# Frankie_DIYRevC.net
KiCad netlist of a schematic drawn in EAGLE
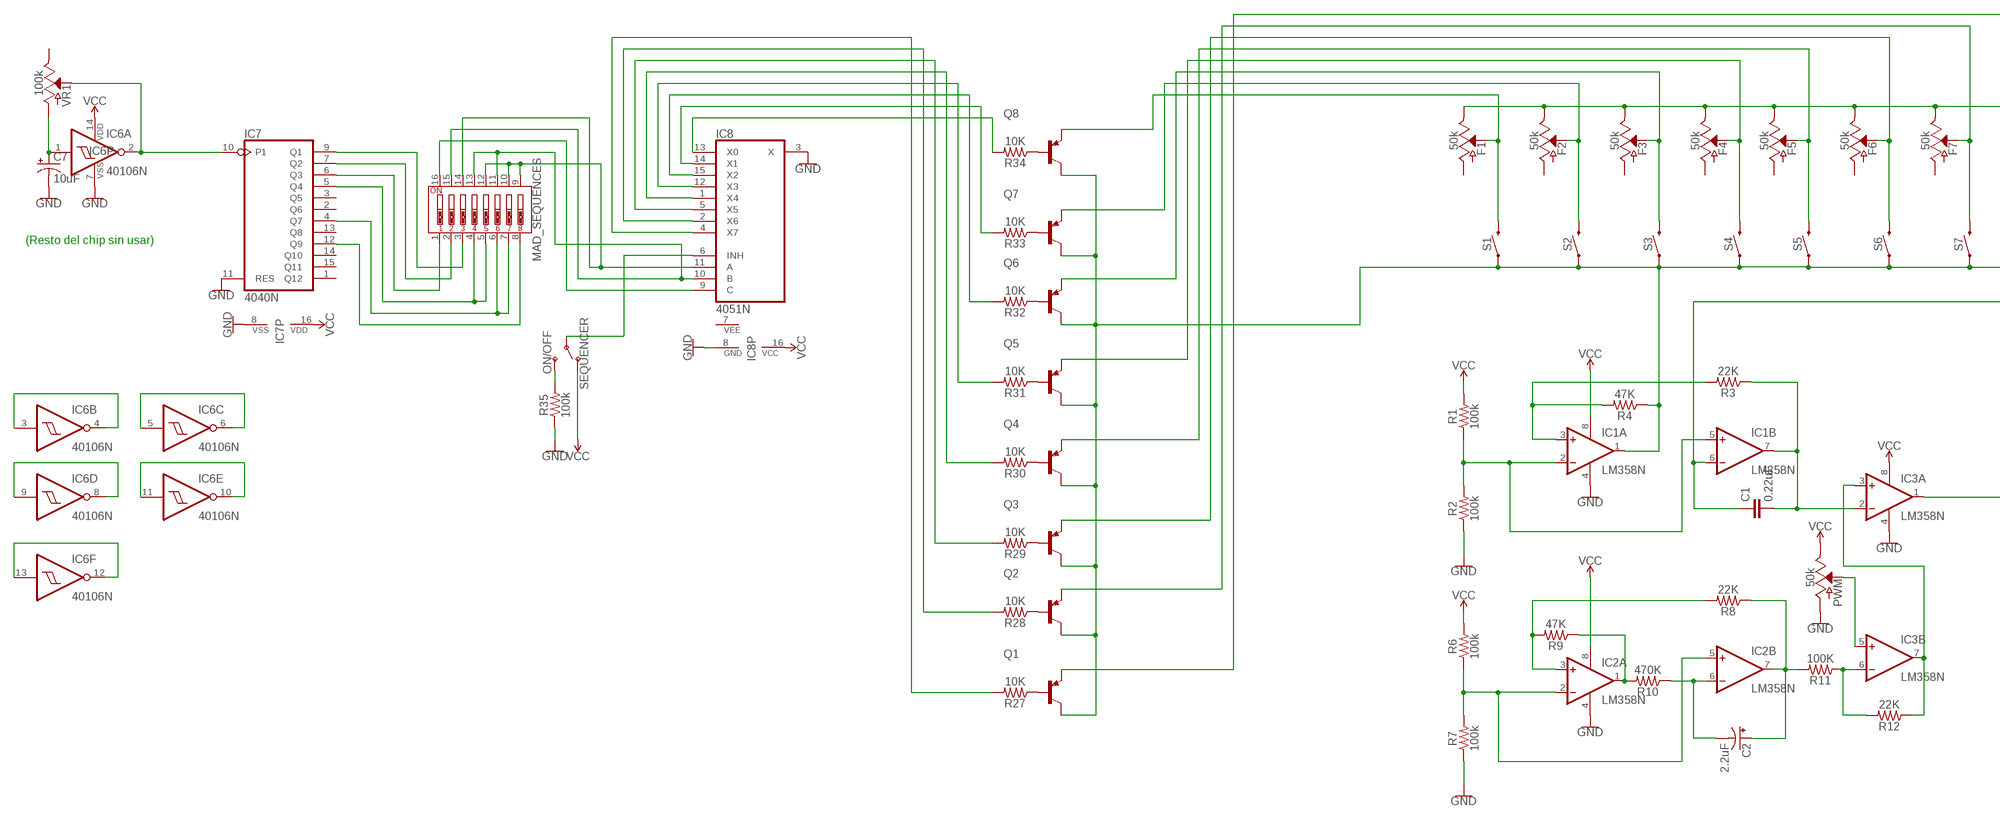
[diagram p0: schematic, sheet 1, part 1 of 2]
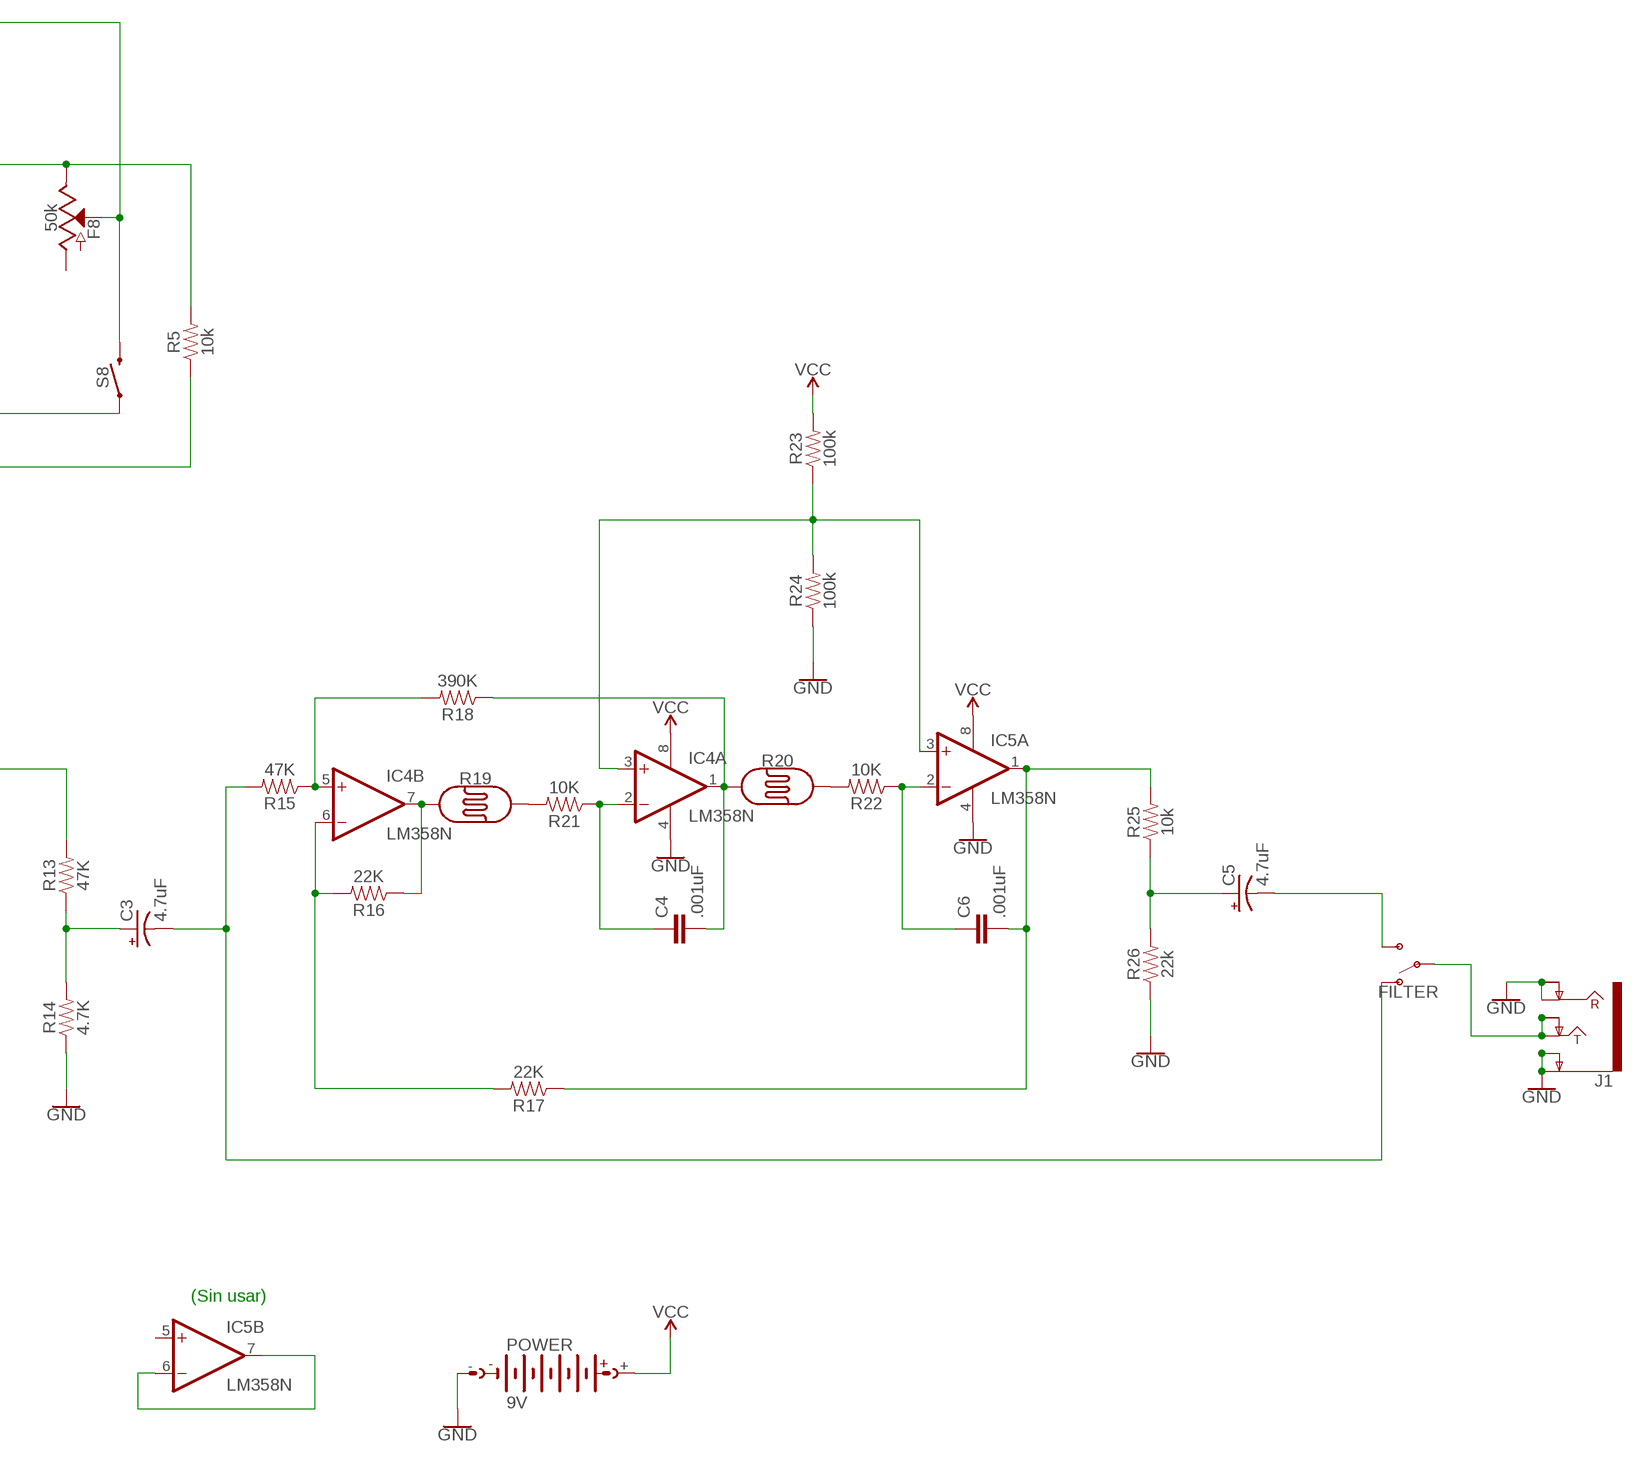
[diagram p1: schematic, sheet 1, part 2 of 2]

(export (version "E")
  (design (tool "Eeschema 10.0.6"))
  (components
    (comp (ref "C1")
      (value "0.22uF")
      (footprint "eagle-import:C5B2.5")
      (libsource (lib "eagle-import") (part "C5/2.5"))
    )
    (comp (ref "C2")
      (value "2.2uF")
      (footprint "eagle-import:CPOL-RADIAL-2.5MM-5MM-KIT")
      (libsource (lib "eagle-import") (part "10UF-POLAR-RADIAL-2.5MM-KIT-25V-20%"))
    )
    (comp (ref "C3")
      (value "4.7uF")
      (footprint "eagle-import:CPOL-RADIAL-2.5MM-5MM-KIT")
      (libsource (lib "eagle-import") (part "10UF-POLAR-RADIAL-2.5MM-KIT-25V-20%"))
    )
    (comp (ref "C4")
      (value ".001uF")
      (footprint "eagle-import:C5B2.5")
      (libsource (lib "eagle-import") (part "C5/2.5"))
    )
    (comp (ref "C5")
      (value "4.7uF")
      (footprint "eagle-import:CPOL-RADIAL-2.5MM-5MM-KIT")
      (libsource (lib "eagle-import") (part "10UF-POLAR-RADIAL-2.5MM-KIT-25V-20%"))
    )
    (comp (ref "C6")
      (value ".001uF")
      (footprint "eagle-import:C5B2.5")
      (libsource (lib "eagle-import") (part "C5/2.5"))
    )
    (comp (ref "C7")
      (value "10uF")
      (footprint "eagle-import:CPOL-RADIAL-2.5MM-5MM-KIT")
      (libsource (lib "eagle-import") (part "10UF-POLAR-RADIAL-2.5MM-KIT-25V-20%"))
    )
    (comp (ref "F1")
      (value "50k")
      (footprint "eagle-import:POT-PTH-ALPS-KIT")
      (libsource (lib "eagle-import") (part "POTENTIOMETER-PTH-9MM-1/20W-20%-KIT"))
    )
    (comp (ref "F2")
      (value "50k")
      (footprint "eagle-import:POT-PTH-ALPS-KIT")
      (libsource (lib "eagle-import") (part "POTENTIOMETER-PTH-9MM-1/20W-20%-KIT"))
    )
    (comp (ref "F3")
      (value "50k")
      (footprint "eagle-import:POT-PTH-ALPS-KIT")
      (libsource (lib "eagle-import") (part "POTENTIOMETER-PTH-9MM-1/20W-20%-KIT"))
    )
    (comp (ref "F4")
      (value "50k")
      (footprint "eagle-import:POT-PTH-ALPS-KIT")
      (libsource (lib "eagle-import") (part "POTENTIOMETER-PTH-9MM-1/20W-20%-KIT"))
    )
    (comp (ref "F5")
      (value "50k")
      (footprint "eagle-import:POT-PTH-ALPS-KIT")
      (libsource (lib "eagle-import") (part "POTENTIOMETER-PTH-9MM-1/20W-20%-KIT"))
    )
    (comp (ref "F6")
      (value "50k")
      (footprint "eagle-import:POT-PTH-ALPS-KIT")
      (libsource (lib "eagle-import") (part "POTENTIOMETER-PTH-9MM-1/20W-20%-KIT"))
    )
    (comp (ref "F7")
      (value "50k")
      (footprint "eagle-import:POT-PTH-ALPS-KIT")
      (libsource (lib "eagle-import") (part "POTENTIOMETER-PTH-9MM-1/20W-20%-KIT"))
    )
    (comp (ref "F8")
      (value "50k")
      (footprint "eagle-import:POT-PTH-ALPS-KIT")
      (libsource (lib "eagle-import") (part "POTENTIOMETER-PTH-9MM-1/20W-20%-KIT"))
    )
    (comp (ref "FILTER")
      (value "SWITCH-SPDT-PTH-11.6X4.0MM-KIT")
      (footprint "eagle-import:SWITCH_SPDT_PTH_11.6X4.0MM_KIT")
      (libsource (lib "eagle-import") (part "SWITCH-SPDT-PTH-11.6X4.0MM-KIT"))
    )
    (comp (ref "IC1")
      (value "LM358N")
      (footprint "eagle-import:DIL08")
      (libsource (lib "eagle-import") (part "LM358N"))
    )
    (comp (ref "IC2")
      (value "LM358N")
      (footprint "eagle-import:DIL08")
      (libsource (lib "eagle-import") (part "LM358N"))
    )
    (comp (ref "IC3")
      (value "LM358N")
      (footprint "eagle-import:DIL08")
      (libsource (lib "eagle-import") (part "LM358N"))
    )
    (comp (ref "IC4")
      (value "LM358N")
      (footprint "eagle-import:DIL08")
      (libsource (lib "eagle-import") (part "LM358N"))
    )
    (comp (ref "IC5")
      (value "LM358N")
      (footprint "eagle-import:DIL08")
      (libsource (lib "eagle-import") (part "LM358N"))
    )
    (comp (ref "IC6")
      (value "40106N")
      (footprint "eagle-import:DIL14")
      (libsource (lib "eagle-import") (part "40106N"))
    )
    (comp (ref "IC7")
      (value "4040N")
      (footprint "eagle-import:DIL16")
      (libsource (lib "eagle-import") (part "4040N"))
    )
    (comp (ref "IC8")
      (value "4051N")
      (footprint "eagle-import:DIL16")
      (libsource (lib "eagle-import") (part "4051N"))
    )
    (comp (ref "J1")
      (value "AUDIO_JACK_TRS_0.25\"_PTH_RA")
      (footprint "eagle-import:AUDIO_JACK_0.25__TRS_PTH_RA")
      (libsource (lib "eagle-import") (part "AUDIO_JACK_TRS_0.25{dblquote}_PTH_RA"))
    )
    (comp (ref "MAD_SEQUENCES")
      (value "DIP-08-PTH")
      (footprint "eagle-import:DIPSWITCH-08")
      (libsource (lib "eagle-import") (part "DIP-08-PTH"))
    )
    (comp (ref "POWER")
      (value "9V")
      (footprint "eagle-import:AB9V")
      (libsource (lib "eagle-import") (part "AB9V"))
    )
    (comp (ref "PWM")
      (value "50k")
      (footprint "eagle-import:POT-PTH-ALPS-KIT")
      (libsource (lib "eagle-import") (part "POTENTIOMETER-PTH-9MM-1/20W-20%-KIT"))
    )
    (comp (ref "Q1")
      (value "2N3906")
      (footprint "eagle-import:TO92")
      (libsource (lib "eagle-import") (part "2N3906"))
    )
    (comp (ref "Q2")
      (value "2N3906")
      (footprint "eagle-import:TO92")
      (libsource (lib "eagle-import") (part "2N3906"))
    )
    (comp (ref "Q3")
      (value "2N3906")
      (footprint "eagle-import:TO92")
      (libsource (lib "eagle-import") (part "2N3906"))
    )
    (comp (ref "Q4")
      (value "2N3906")
      (footprint "eagle-import:TO92")
      (libsource (lib "eagle-import") (part "2N3906"))
    )
    (comp (ref "Q5")
      (value "2N3906")
      (footprint "eagle-import:TO92")
      (libsource (lib "eagle-import") (part "2N3906"))
    )
    (comp (ref "Q6")
      (value "2N3906")
      (footprint "eagle-import:TO92")
      (libsource (lib "eagle-import") (part "2N3906"))
    )
    (comp (ref "Q7")
      (value "2N3906")
      (footprint "eagle-import:TO92")
      (libsource (lib "eagle-import") (part "2N3906"))
    )
    (comp (ref "Q8")
      (value "2N3906")
      (footprint "eagle-import:TO92")
      (libsource (lib "eagle-import") (part "2N3906"))
    )
    (comp (ref "R1")
      (value "100k")
      (footprint "eagle-import:AXIAL-0.3")
      (libsource (lib "eagle-import") (part "100KOHM-HORIZ-1/4W-5%"))
    )
    (comp (ref "R2")
      (value "100k")
      (footprint "eagle-import:AXIAL-0.3")
      (libsource (lib "eagle-import") (part "100KOHM-HORIZ-1/4W-5%"))
    )
    (comp (ref "R3")
      (value "22K")
      (footprint "eagle-import:AXIAL-0.3")
      (libsource (lib "eagle-import") (part "100KOHM-HORIZ-1/4W-5%"))
    )
    (comp (ref "R4")
      (value "47K")
      (footprint "eagle-import:AXIAL-0.3")
      (libsource (lib "eagle-import") (part "100KOHM-HORIZ-1/4W-5%"))
    )
    (comp (ref "R5")
      (value "10k")
      (footprint "eagle-import:AXIAL-0.3")
      (libsource (lib "eagle-import") (part "100KOHM-HORIZ-1/4W-5%"))
    )
    (comp (ref "R6")
      (value "100k")
      (footprint "eagle-import:AXIAL-0.3")
      (libsource (lib "eagle-import") (part "100KOHM-HORIZ-1/4W-5%"))
    )
    (comp (ref "R7")
      (value "100k")
      (footprint "eagle-import:AXIAL-0.3")
      (libsource (lib "eagle-import") (part "100KOHM-HORIZ-1/4W-5%"))
    )
    (comp (ref "R8")
      (value "22K")
      (footprint "eagle-import:AXIAL-0.3")
      (libsource (lib "eagle-import") (part "100KOHM-HORIZ-1/4W-5%"))
    )
    (comp (ref "R9")
      (value "47K")
      (footprint "eagle-import:AXIAL-0.3")
      (libsource (lib "eagle-import") (part "100KOHM-HORIZ-1/4W-5%"))
    )
    (comp (ref "R10")
      (value "470K")
      (footprint "eagle-import:AXIAL-0.3")
      (libsource (lib "eagle-import") (part "100KOHM-HORIZ-1/4W-5%"))
    )
    (comp (ref "R11")
      (value "100K")
      (footprint "eagle-import:AXIAL-0.3")
      (libsource (lib "eagle-import") (part "100KOHM-HORIZ-1/4W-5%"))
    )
    (comp (ref "R12")
      (value "22K")
      (footprint "eagle-import:AXIAL-0.3")
      (libsource (lib "eagle-import") (part "100KOHM-HORIZ-1/4W-5%"))
    )
    (comp (ref "R13")
      (value "47K")
      (footprint "eagle-import:AXIAL-0.3")
      (libsource (lib "eagle-import") (part "100KOHM-HORIZ-1/4W-5%"))
    )
    (comp (ref "R14")
      (value "4.7K")
      (footprint "eagle-import:AXIAL-0.3")
      (libsource (lib "eagle-import") (part "100KOHM-HORIZ-1/4W-5%"))
    )
    (comp (ref "R15")
      (value "47K")
      (footprint "eagle-import:AXIAL-0.3")
      (libsource (lib "eagle-import") (part "100KOHM-HORIZ-1/4W-5%"))
    )
    (comp (ref "R16")
      (value "22K")
      (footprint "eagle-import:AXIAL-0.3")
      (libsource (lib "eagle-import") (part "100KOHM-HORIZ-1/4W-5%"))
    )
    (comp (ref "R17")
      (value "22K")
      (footprint "eagle-import:AXIAL-0.3")
      (libsource (lib "eagle-import") (part "100KOHM-HORIZ-1/4W-5%"))
    )
    (comp (ref "R18")
      (value "390K")
      (footprint "eagle-import:AXIAL-0.3")
      (libsource (lib "eagle-import") (part "100KOHM-HORIZ-1/4W-5%"))
    )
    (comp (ref "R19")
      (value "PHOTOCELLPTH-KIT")
      (footprint "eagle-import:PHOTOCELL-KIT")
      (libsource (lib "eagle-import") (part "PHOTOCELLPTH-KIT"))
    )
    (comp (ref "R20")
      (value "PHOTOCELLPTH-KIT")
      (footprint "eagle-import:PHOTOCELL-KIT")
      (libsource (lib "eagle-import") (part "PHOTOCELLPTH-KIT"))
    )
    (comp (ref "R21")
      (value "10K")
      (footprint "eagle-import:AXIAL-0.3")
      (libsource (lib "eagle-import") (part "100KOHM-HORIZ-1/4W-5%"))
    )
    (comp (ref "R22")
      (value "10K")
      (footprint "eagle-import:AXIAL-0.3")
      (libsource (lib "eagle-import") (part "100KOHM-HORIZ-1/4W-5%"))
    )
    (comp (ref "R23")
      (value "100k")
      (footprint "eagle-import:AXIAL-0.3")
      (libsource (lib "eagle-import") (part "100KOHM-HORIZ-1/4W-5%"))
    )
    (comp (ref "R24")
      (value "100k")
      (footprint "eagle-import:AXIAL-0.3")
      (libsource (lib "eagle-import") (part "100KOHM-HORIZ-1/4W-5%"))
    )
    (comp (ref "R25")
      (value "10k")
      (footprint "eagle-import:AXIAL-0.3")
      (libsource (lib "eagle-import") (part "100KOHM-HORIZ-1/4W-5%"))
    )
    (comp (ref "R26")
      (value "22k")
      (footprint "eagle-import:AXIAL-0.3")
      (libsource (lib "eagle-import") (part "100KOHM-HORIZ-1/4W-5%"))
    )
    (comp (ref "R27")
      (value "10K")
      (footprint "eagle-import:AXIAL-0.3")
      (libsource (lib "eagle-import") (part "100KOHM-HORIZ-1/4W-5%"))
    )
    (comp (ref "R28")
      (value "10K")
      (footprint "eagle-import:AXIAL-0.3")
      (libsource (lib "eagle-import") (part "100KOHM-HORIZ-1/4W-5%"))
    )
    (comp (ref "R29")
      (value "10K")
      (footprint "eagle-import:AXIAL-0.3")
      (libsource (lib "eagle-import") (part "100KOHM-HORIZ-1/4W-5%"))
    )
    (comp (ref "R30")
      (value "10K")
      (footprint "eagle-import:AXIAL-0.3")
      (libsource (lib "eagle-import") (part "100KOHM-HORIZ-1/4W-5%"))
    )
    (comp (ref "R31")
      (value "10K")
      (footprint "eagle-import:AXIAL-0.3")
      (libsource (lib "eagle-import") (part "100KOHM-HORIZ-1/4W-5%"))
    )
    (comp (ref "R32")
      (value "10K")
      (footprint "eagle-import:AXIAL-0.3")
      (libsource (lib "eagle-import") (part "100KOHM-HORIZ-1/4W-5%"))
    )
    (comp (ref "R33")
      (value "10K")
      (footprint "eagle-import:AXIAL-0.3")
      (libsource (lib "eagle-import") (part "100KOHM-HORIZ-1/4W-5%"))
    )
    (comp (ref "R34")
      (value "10K")
      (footprint "eagle-import:AXIAL-0.3")
      (libsource (lib "eagle-import") (part "100KOHM-HORIZ-1/4W-5%"))
    )
    (comp (ref "R35")
      (value "100k")
      (footprint "eagle-import:AXIAL-0.3")
      (libsource (lib "eagle-import") (part "100KOHM-HORIZ-1/4W-5%"))
    )
    (comp (ref "S1")
      (value "MOMENTARY-SWITCH-SPST-PTH-12MM")
      (footprint "eagle-import:TACTILE_SWITCH_PTH_12MM")
      (libsource (lib "eagle-import") (part "MOMENTARY-SWITCH-SPST-PTH-12MM"))
    )
    (comp (ref "S2")
      (value "MOMENTARY-SWITCH-SPST-PTH-12MM")
      (footprint "eagle-import:TACTILE_SWITCH_PTH_12MM")
      (libsource (lib "eagle-import") (part "MOMENTARY-SWITCH-SPST-PTH-12MM"))
    )
    (comp (ref "S3")
      (value "MOMENTARY-SWITCH-SPST-PTH-12MM")
      (footprint "eagle-import:TACTILE_SWITCH_PTH_12MM")
      (libsource (lib "eagle-import") (part "MOMENTARY-SWITCH-SPST-PTH-12MM"))
    )
    (comp (ref "S4")
      (value "MOMENTARY-SWITCH-SPST-PTH-12MM")
      (footprint "eagle-import:TACTILE_SWITCH_PTH_12MM")
      (libsource (lib "eagle-import") (part "MOMENTARY-SWITCH-SPST-PTH-12MM"))
    )
    (comp (ref "S5")
      (value "MOMENTARY-SWITCH-SPST-PTH-12MM")
      (footprint "eagle-import:TACTILE_SWITCH_PTH_12MM")
      (libsource (lib "eagle-import") (part "MOMENTARY-SWITCH-SPST-PTH-12MM"))
    )
    (comp (ref "S6")
      (value "MOMENTARY-SWITCH-SPST-PTH-12MM")
      (footprint "eagle-import:TACTILE_SWITCH_PTH_12MM")
      (libsource (lib "eagle-import") (part "MOMENTARY-SWITCH-SPST-PTH-12MM"))
    )
    (comp (ref "S7")
      (value "MOMENTARY-SWITCH-SPST-PTH-12MM")
      (footprint "eagle-import:TACTILE_SWITCH_PTH_12MM")
      (libsource (lib "eagle-import") (part "MOMENTARY-SWITCH-SPST-PTH-12MM"))
    )
    (comp (ref "S8")
      (value "MOMENTARY-SWITCH-SPST-PTH-12MM")
      (footprint "eagle-import:TACTILE_SWITCH_PTH_12MM")
      (libsource (lib "eagle-import") (part "MOMENTARY-SWITCH-SPST-PTH-12MM"))
    )
    (comp (ref "SEQUENCER")
      (value "ON/OFF")
      (footprint "eagle-import:SWITCH_SPDT_PTH_11.6X4.0MM_KIT")
      (libsource (lib "eagle-import") (part "SWITCH-SPDT-PTH-11.6X4.0MM-KIT"))
    )
    (comp (ref "VR1")
      (value "100k")
      (footprint "eagle-import:POT-PTH-ALPS-KIT")
      (libsource (lib "eagle-import") (part "POTENTIOMETER-PTH-9MM-1/20W-20%-KIT"))
    )
  )
  (nets
    (net (code "1") (name "/VEE") (class "Default")
      (node (ref "IC8") (pin "7") (pinfunction "VEE_7") (pintype "power_in"))
    )
    (net (code "2") (name "GND") (class "Default")
      (node (ref "C7") (pin "2") (pinfunction "-_2") (pintype "passive"))
      (node (ref "IC1") (pin "4") (pinfunction "V-_4") (pintype "power_in"))
      (node (ref "IC2") (pin "4") (pinfunction "V-_4") (pintype "power_in"))
      (node (ref "IC3") (pin "4") (pinfunction "V-_4") (pintype "power_in"))
      (node (ref "IC4") (pin "4") (pinfunction "V-_4") (pintype "power_in"))
      (node (ref "IC5") (pin "4") (pinfunction "V-_4") (pintype "power_in"))
      (node (ref "IC6") (pin "7") (pinfunction "VSS_7") (pintype "power_in"))
      (node (ref "IC7") (pin "11") (pinfunction "RES_11") (pintype "input"))
      (node (ref "IC7") (pin "8") (pinfunction "VSS_8") (pintype "power_in"))
      (node (ref "IC8") (pin "3") (pinfunction "X_3") (pintype "bidirectional"))
      (node (ref "IC8") (pin "8") (pinfunction "GND_8") (pintype "power_in"))
      (node (ref "J1") (pin "RING") (pinfunction "RING_RING") (pintype "bidirectional"))
      (node (ref "J1") (pin "RING-NORM") (pinfunction "RING-NORM_RING-NORM") (pintype "bidirectional"))
      (node (ref "J1") (pin "SLEEVE") (pinfunction "EARTH_SLEEVE") (pintype "bidirectional"))
      (node (ref "J1") (pin "SLEEVE-NORM") (pinfunction "EARTH-NORM_SLEEVE-NORM") (pintype "bidirectional"))
      (node (ref "POWER") (pin "-") (pinfunction "-_-") (pintype "passive"))
      (node (ref "PWM") (pin "P$3") (pinfunction "A_P$3") (pintype "passive"))
      (node (ref "R14") (pin "P$1") (pinfunction "1_P$1") (pintype "passive"))
      (node (ref "R2") (pin "P$1") (pinfunction "1_P$1") (pintype "passive"))
      (node (ref "R24") (pin "P$1") (pinfunction "1_P$1") (pintype "passive"))
      (node (ref "R26") (pin "P$1") (pinfunction "1_P$1") (pintype "passive"))
      (node (ref "R35") (pin "P$1") (pinfunction "1_P$1") (pintype "passive"))
      (node (ref "R7") (pin "P$1") (pinfunction "1_P$1") (pintype "passive"))
    )
    (net (code "3") (name "Net-(C2-+)") (class "Default")
      (node (ref "C2") (pin "1") (pinfunction "+_1") (pintype "passive"))
      (node (ref "IC2") (pin "7") (pinfunction "OUT_7") (pintype "output"))
      (node (ref "R11") (pin "P$2") (pinfunction "2_P$2") (pintype "passive"))
      (node (ref "R8") (pin "P$1") (pinfunction "1_P$1") (pintype "passive"))
    )
    (net (code "4") (name "Net-(C2--)") (class "Default")
      (node (ref "C2") (pin "2") (pinfunction "-_2") (pintype "passive"))
      (node (ref "IC2") (pin "6") (pinfunction "-IN_6") (pintype "input"))
      (node (ref "R10") (pin "P$1") (pinfunction "1_P$1") (pintype "passive"))
    )
    (net (code "5") (name "Net-(C3-+)") (class "Default")
      (node (ref "C3") (pin "1") (pinfunction "+_1") (pintype "passive"))
      (node (ref "R13") (pin "P$1") (pinfunction "1_P$1") (pintype "passive"))
      (node (ref "R14") (pin "P$2") (pinfunction "2_P$2") (pintype "passive"))
    )
    (net (code "6") (name "Net-(C3--)") (class "Default")
      (node (ref "C3") (pin "2") (pinfunction "-_2") (pintype "passive"))
      (node (ref "FILTER") (pin "1") (pinfunction "O_1") (pintype "passive"))
      (node (ref "R15") (pin "P$2") (pinfunction "2_P$2") (pintype "passive"))
    )
    (net (code "7") (name "Net-(C5-+)") (class "Default")
      (node (ref "C5") (pin "1") (pinfunction "+_1") (pintype "passive"))
      (node (ref "R25") (pin "P$1") (pinfunction "1_P$1") (pintype "passive"))
      (node (ref "R26") (pin "P$2") (pinfunction "2_P$2") (pintype "passive"))
    )
    (net (code "8") (name "Net-(C5--)") (class "Default")
      (node (ref "C5") (pin "2") (pinfunction "-_2") (pintype "passive"))
      (node (ref "FILTER") (pin "3") (pinfunction "S_3") (pintype "passive"))
    )
    (net (code "9") (name "Net-(C7-+)") (class "Default")
      (node (ref "C7") (pin "1") (pinfunction "+_1") (pintype "passive"))
      (node (ref "IC6") (pin "1") (pinfunction "I_1") (pintype "input"))
      (node (ref "VR1") (pin "P$3") (pinfunction "A_P$3") (pintype "passive"))
    )
    (net (code "10") (name "Net-(F1-E)") (class "Default")
      (node (ref "F1") (pin "P$1") (pinfunction "E_P$1") (pintype "passive"))
      (node (ref "F2") (pin "P$1") (pinfunction "E_P$1") (pintype "passive"))
      (node (ref "F3") (pin "P$1") (pinfunction "E_P$1") (pintype "passive"))
      (node (ref "F4") (pin "P$1") (pinfunction "E_P$1") (pintype "passive"))
      (node (ref "F5") (pin "P$1") (pinfunction "E_P$1") (pintype "passive"))
      (node (ref "F6") (pin "P$1") (pinfunction "E_P$1") (pintype "passive"))
      (node (ref "F7") (pin "P$1") (pinfunction "E_P$1") (pintype "passive"))
      (node (ref "F8") (pin "P$1") (pinfunction "E_P$1") (pintype "passive"))
      (node (ref "R5") (pin "P$2") (pinfunction "2_P$2") (pintype "passive"))
    )
    (net (code "11") (name "Net-(F1-S)") (class "Default")
      (node (ref "F1") (pin "P$2") (pinfunction "S_P$2") (pintype "passive"))
      (node (ref "Q8") (pin "3") (pinfunction "E_3") (pintype "passive"))
      (node (ref "S1") (pin "3") (pinfunction "2_3") (pintype "passive"))
    )
    (net (code "12") (name "Net-(F2-S)") (class "Default")
      (node (ref "F2") (pin "P$2") (pinfunction "S_P$2") (pintype "passive"))
      (node (ref "Q7") (pin "3") (pinfunction "E_3") (pintype "passive"))
      (node (ref "S2") (pin "3") (pinfunction "2_3") (pintype "passive"))
    )
    (net (code "13") (name "Net-(F3-S)") (class "Default")
      (node (ref "F3") (pin "P$2") (pinfunction "S_P$2") (pintype "passive"))
      (node (ref "Q6") (pin "3") (pinfunction "E_3") (pintype "passive"))
      (node (ref "S3") (pin "3") (pinfunction "2_3") (pintype "passive"))
    )
    (net (code "14") (name "Net-(F4-S)") (class "Default")
      (node (ref "F4") (pin "P$2") (pinfunction "S_P$2") (pintype "passive"))
      (node (ref "Q5") (pin "3") (pinfunction "E_3") (pintype "passive"))
      (node (ref "S4") (pin "3") (pinfunction "2_3") (pintype "passive"))
    )
    (net (code "15") (name "Net-(F5-S)") (class "Default")
      (node (ref "F5") (pin "P$2") (pinfunction "S_P$2") (pintype "passive"))
      (node (ref "Q4") (pin "3") (pinfunction "E_3") (pintype "passive"))
      (node (ref "S5") (pin "3") (pinfunction "2_3") (pintype "passive"))
    )
    (net (code "16") (name "Net-(F6-S)") (class "Default")
      (node (ref "F6") (pin "P$2") (pinfunction "S_P$2") (pintype "passive"))
      (node (ref "Q3") (pin "3") (pinfunction "E_3") (pintype "passive"))
      (node (ref "S6") (pin "3") (pinfunction "2_3") (pintype "passive"))
    )
    (net (code "17") (name "Net-(F7-S)") (class "Default")
      (node (ref "F7") (pin "P$2") (pinfunction "S_P$2") (pintype "passive"))
      (node (ref "Q2") (pin "3") (pinfunction "E_3") (pintype "passive"))
      (node (ref "S7") (pin "3") (pinfunction "2_3") (pintype "passive"))
    )
    (net (code "18") (name "Net-(F8-S)") (class "Default")
      (node (ref "F8") (pin "P$2") (pinfunction "S_P$2") (pintype "passive"))
      (node (ref "Q1") (pin "3") (pinfunction "E_3") (pintype "passive"))
      (node (ref "S8") (pin "3") (pinfunction "2_3") (pintype "passive"))
    )
    (net (code "19") (name "Net-(FILTER-P)") (class "Default")
      (node (ref "FILTER") (pin "2") (pinfunction "P_2") (pintype "passive"))
      (node (ref "J1") (pin "TIP") (pinfunction "TIP_TIP") (pintype "bidirectional"))
      (node (ref "J1") (pin "TIP-NORM") (pinfunction "TIP-NORM_TIP-NORM") (pintype "bidirectional"))
    )
    (net (code "20") (name "Net-(IC1A-+IN)") (class "Default")
      (node (ref "IC1") (pin "3") (pinfunction "+IN_3") (pintype "input"))
      (node (ref "R3") (pin "P$2") (pinfunction "2_P$2") (pintype "passive"))
      (node (ref "R4") (pin "P$2") (pinfunction "2_P$2") (pintype "passive"))
    )
    (net (code "21") (name "Net-(IC1A--IN)") (class "Default")
      (node (ref "IC1") (pin "2") (pinfunction "-IN_2") (pintype "input"))
      (node (ref "IC1") (pin "5") (pinfunction "+IN_5") (pintype "input"))
      (node (ref "R1") (pin "P$1") (pinfunction "1_P$1") (pintype "passive"))
      (node (ref "R2") (pin "P$2") (pinfunction "2_P$2") (pintype "passive"))
    )
    (net (code "22") (name "Net-(IC1A-OUT)") (class "Default")
      (node (ref "IC1") (pin "1") (pinfunction "OUT_1") (pintype "output"))
      (node (ref "Q1") (pin "1") (pinfunction "C_1") (pintype "passive"))
      (node (ref "Q2") (pin "1") (pinfunction "C_1") (pintype "passive"))
      (node (ref "Q3") (pin "1") (pinfunction "C_1") (pintype "passive"))
      (node (ref "Q4") (pin "1") (pinfunction "C_1") (pintype "passive"))
      (node (ref "Q5") (pin "1") (pinfunction "C_1") (pintype "passive"))
      (node (ref "Q6") (pin "1") (pinfunction "C_1") (pintype "passive"))
      (node (ref "Q7") (pin "1") (pinfunction "C_1") (pintype "passive"))
      (node (ref "Q8") (pin "1") (pinfunction "C_1") (pintype "passive"))
      (node (ref "R4") (pin "P$1") (pinfunction "1_P$1") (pintype "passive"))
      (node (ref "S1") (pin "1") (pinfunction "1_1") (pintype "passive"))
      (node (ref "S2") (pin "1") (pinfunction "1_1") (pintype "passive"))
      (node (ref "S3") (pin "1") (pinfunction "1_1") (pintype "passive"))
      (node (ref "S4") (pin "1") (pinfunction "1_1") (pintype "passive"))
      (node (ref "S5") (pin "1") (pinfunction "1_1") (pintype "passive"))
      (node (ref "S6") (pin "1") (pinfunction "1_1") (pintype "passive"))
      (node (ref "S7") (pin "1") (pinfunction "1_1") (pintype "passive"))
      (node (ref "S8") (pin "1") (pinfunction "1_1") (pintype "passive"))
    )
    (net (code "23") (name "Net-(IC1B--IN)") (class "Default")
      (node (ref "C1") (pin "1") (pinfunction "1_1") (pintype "passive"))
      (node (ref "IC1") (pin "6") (pinfunction "-IN_6") (pintype "input"))
      (node (ref "R5") (pin "P$1") (pinfunction "1_P$1") (pintype "passive"))
    )
    (net (code "24") (name "Net-(IC1B-OUT)") (class "Default")
      (node (ref "C1") (pin "2") (pinfunction "2_2") (pintype "passive"))
      (node (ref "IC1") (pin "7") (pinfunction "OUT_7") (pintype "output"))
      (node (ref "IC3") (pin "2") (pinfunction "-IN_2") (pintype "input"))
      (node (ref "R3") (pin "P$1") (pinfunction "1_P$1") (pintype "passive"))
    )
    (net (code "25") (name "Net-(IC2A-+IN)") (class "Default")
      (node (ref "IC2") (pin "3") (pinfunction "+IN_3") (pintype "input"))
      (node (ref "R8") (pin "P$2") (pinfunction "2_P$2") (pintype "passive"))
      (node (ref "R9") (pin "P$2") (pinfunction "2_P$2") (pintype "passive"))
    )
    (net (code "26") (name "Net-(IC2A--IN)") (class "Default")
      (node (ref "IC2") (pin "2") (pinfunction "-IN_2") (pintype "input"))
      (node (ref "IC2") (pin "5") (pinfunction "+IN_5") (pintype "input"))
      (node (ref "R6") (pin "P$1") (pinfunction "1_P$1") (pintype "passive"))
      (node (ref "R7") (pin "P$2") (pinfunction "2_P$2") (pintype "passive"))
    )
    (net (code "27") (name "Net-(IC2A-OUT)") (class "Default")
      (node (ref "IC2") (pin "1") (pinfunction "OUT_1") (pintype "output"))
      (node (ref "R10") (pin "P$2") (pinfunction "2_P$2") (pintype "passive"))
      (node (ref "R9") (pin "P$1") (pinfunction "1_P$1") (pintype "passive"))
    )
    (net (code "28") (name "Net-(IC3A-+IN)") (class "Default")
      (node (ref "IC3") (pin "3") (pinfunction "+IN_3") (pintype "input"))
      (node (ref "IC3") (pin "7") (pinfunction "OUT_7") (pintype "output"))
      (node (ref "R12") (pin "P$1") (pinfunction "1_P$1") (pintype "passive"))
    )
    (net (code "29") (name "Net-(IC3A-OUT)") (class "Default")
      (node (ref "IC3") (pin "1") (pinfunction "OUT_1") (pintype "output"))
      (node (ref "R13") (pin "P$2") (pinfunction "2_P$2") (pintype "passive"))
    )
    (net (code "30") (name "Net-(IC3B-+IN)") (class "Default")
      (node (ref "IC3") (pin "5") (pinfunction "+IN_5") (pintype "input"))
      (node (ref "PWM") (pin "P$2") (pinfunction "S_P$2") (pintype "passive"))
    )
    (net (code "31") (name "Net-(IC3B--IN)") (class "Default")
      (node (ref "IC3") (pin "6") (pinfunction "-IN_6") (pintype "input"))
      (node (ref "R11") (pin "P$1") (pinfunction "1_P$1") (pintype "passive"))
      (node (ref "R12") (pin "P$2") (pinfunction "2_P$2") (pintype "passive"))
    )
    (net (code "32") (name "Net-(IC4A-+IN)") (class "Default")
      (node (ref "IC4") (pin "3") (pinfunction "+IN_3") (pintype "input"))
      (node (ref "IC5") (pin "3") (pinfunction "+IN_3") (pintype "input"))
      (node (ref "R23") (pin "P$1") (pinfunction "1_P$1") (pintype "passive"))
      (node (ref "R24") (pin "P$2") (pinfunction "2_P$2") (pintype "passive"))
    )
    (net (code "33") (name "Net-(IC4A--IN)") (class "Default")
      (node (ref "C4") (pin "1") (pinfunction "1_1") (pintype "passive"))
      (node (ref "IC4") (pin "2") (pinfunction "-IN_2") (pintype "input"))
      (node (ref "R21") (pin "P$1") (pinfunction "1_P$1") (pintype "passive"))
    )
    (net (code "34") (name "Net-(IC4A-OUT)") (class "Default")
      (node (ref "C4") (pin "2") (pinfunction "2_2") (pintype "passive"))
      (node (ref "IC4") (pin "1") (pinfunction "OUT_1") (pintype "output"))
      (node (ref "R18") (pin "P$1") (pinfunction "1_P$1") (pintype "passive"))
      (node (ref "R20") (pin "1") (pinfunction "P$1_1") (pintype "bidirectional"))
    )
    (net (code "35") (name "Net-(IC4B-+IN)") (class "Default")
      (node (ref "IC4") (pin "5") (pinfunction "+IN_5") (pintype "input"))
      (node (ref "R15") (pin "P$1") (pinfunction "1_P$1") (pintype "passive"))
      (node (ref "R18") (pin "P$2") (pinfunction "2_P$2") (pintype "passive"))
    )
    (net (code "36") (name "Net-(IC4B--IN)") (class "Default")
      (node (ref "IC4") (pin "6") (pinfunction "-IN_6") (pintype "input"))
      (node (ref "R16") (pin "P$2") (pinfunction "2_P$2") (pintype "passive"))
      (node (ref "R17") (pin "P$2") (pinfunction "2_P$2") (pintype "passive"))
    )
    (net (code "37") (name "Net-(IC4B-OUT)") (class "Default")
      (node (ref "IC4") (pin "7") (pinfunction "OUT_7") (pintype "output"))
      (node (ref "R16") (pin "P$1") (pinfunction "1_P$1") (pintype "passive"))
      (node (ref "R19") (pin "1") (pinfunction "P$1_1") (pintype "bidirectional"))
    )
    (net (code "38") (name "Net-(IC5A--IN)") (class "Default")
      (node (ref "C6") (pin "1") (pinfunction "1_1") (pintype "passive"))
      (node (ref "IC5") (pin "2") (pinfunction "-IN_2") (pintype "input"))
      (node (ref "R22") (pin "P$1") (pinfunction "1_P$1") (pintype "passive"))
    )
    (net (code "39") (name "Net-(IC5A-OUT)") (class "Default")
      (node (ref "C6") (pin "2") (pinfunction "2_2") (pintype "passive"))
      (node (ref "IC5") (pin "1") (pinfunction "OUT_1") (pintype "output"))
      (node (ref "R17") (pin "P$1") (pinfunction "1_P$1") (pintype "passive"))
      (node (ref "R25") (pin "P$2") (pinfunction "2_P$2") (pintype "passive"))
    )
    (net (code "40") (name "Net-(IC5B--IN)") (class "Default")
      (node (ref "IC5") (pin "6") (pinfunction "-IN_6") (pintype "input"))
      (node (ref "IC5") (pin "7") (pinfunction "OUT_7") (pintype "output"))
    )
    (net (code "41") (name "Net-(IC6A-O)") (class "Default")
      (node (ref "IC6") (pin "2") (pinfunction "O_2") (pintype "output"))
      (node (ref "IC7") (pin "10") (pinfunction "P1_10") (pintype "input"))
      (node (ref "VR1") (pin "P$2") (pinfunction "S_P$2") (pintype "passive"))
    )
    (net (code "42") (name "Net-(IC6B-I)") (class "Default")
      (node (ref "IC6") (pin "3") (pinfunction "I_3") (pintype "input"))
      (node (ref "IC6") (pin "4") (pinfunction "O_4") (pintype "output"))
    )
    (net (code "43") (name "Net-(IC6C-I)") (class "Default")
      (node (ref "IC6") (pin "5") (pinfunction "I_5") (pintype "input"))
      (node (ref "IC6") (pin "6") (pinfunction "O_6") (pintype "output"))
    )
    (net (code "44") (name "Net-(IC6D-I)") (class "Default")
      (node (ref "IC6") (pin "8") (pinfunction "O_8") (pintype "output"))
      (node (ref "IC6") (pin "9") (pinfunction "I_9") (pintype "input"))
    )
    (net (code "45") (name "Net-(IC6E-I)") (class "Default")
      (node (ref "IC6") (pin "10") (pinfunction "O_10") (pintype "output"))
      (node (ref "IC6") (pin "11") (pinfunction "I_11") (pintype "input"))
    )
    (net (code "46") (name "Net-(IC6F-I)") (class "Default")
      (node (ref "IC6") (pin "12") (pinfunction "O_12") (pintype "output"))
      (node (ref "IC6") (pin "13") (pinfunction "I_13") (pintype "input"))
    )
    (net (code "47") (name "Net-(IC7A-Q1)") (class "Default")
      (node (ref "IC7") (pin "9") (pinfunction "Q1_9") (pintype "output"))
      (node (ref "MAD_SEQUENCES") (pin "3") (pinfunction "3_3") (pintype "passive"))
    )
    (net (code "48") (name "Net-(IC7A-Q2)") (class "Default")
      (node (ref "IC7") (pin "7") (pinfunction "Q2_7") (pintype "output"))
      (node (ref "MAD_SEQUENCES") (pin "2") (pinfunction "2_2") (pintype "passive"))
    )
    (net (code "49") (name "Net-(IC7A-Q3)") (class "Default")
      (node (ref "IC7") (pin "6") (pinfunction "Q3_6") (pintype "output"))
      (node (ref "MAD_SEQUENCES") (pin "1") (pinfunction "1_1") (pintype "passive"))
    )
    (net (code "50") (name "Net-(IC7A-Q4)") (class "Default")
      (node (ref "IC7") (pin "5") (pinfunction "Q4_5") (pintype "output"))
      (node (ref "MAD_SEQUENCES") (pin "4") (pinfunction "4_4") (pintype "passive"))
      (node (ref "MAD_SEQUENCES") (pin "5") (pinfunction "5_5") (pintype "passive"))
    )
    (net (code "51") (name "Net-(IC7A-Q7)") (class "Default")
      (node (ref "IC7") (pin "4") (pinfunction "Q7_4") (pintype "output"))
      (node (ref "MAD_SEQUENCES") (pin "6") (pinfunction "6_6") (pintype "passive"))
      (node (ref "MAD_SEQUENCES") (pin "7") (pinfunction "7_7") (pintype "passive"))
    )
    (net (code "52") (name "Net-(IC7A-Q9)") (class "Default")
      (node (ref "IC7") (pin "12") (pinfunction "Q9_12") (pintype "output"))
      (node (ref "MAD_SEQUENCES") (pin "8") (pinfunction "8_8") (pintype "passive"))
    )
    (net (code "53") (name "Net-(IC8A-A)") (class "Default")
      (node (ref "IC8") (pin "11") (pinfunction "A_11") (pintype "input"))
      (node (ref "MAD_SEQUENCES") (pin "10") (pinfunction "10_10") (pintype "passive"))
      (node (ref "MAD_SEQUENCES") (pin "12") (pinfunction "12_12") (pintype "passive"))
      (node (ref "MAD_SEQUENCES") (pin "14") (pinfunction "14_14") (pintype "passive"))
      (node (ref "MAD_SEQUENCES") (pin "9") (pinfunction "9_9") (pintype "passive"))
    )
    (net (code "54") (name "Net-(IC8A-B)") (class "Default")
      (node (ref "IC8") (pin "10") (pinfunction "B_10") (pintype "input"))
      (node (ref "MAD_SEQUENCES") (pin "11") (pinfunction "11_11") (pintype "passive"))
      (node (ref "MAD_SEQUENCES") (pin "13") (pinfunction "13_13") (pintype "passive"))
      (node (ref "MAD_SEQUENCES") (pin "15") (pinfunction "15_15") (pintype "passive"))
    )
    (net (code "55") (name "Net-(IC8A-C)") (class "Default")
      (node (ref "IC8") (pin "9") (pinfunction "C_9") (pintype "input"))
      (node (ref "MAD_SEQUENCES") (pin "16") (pinfunction "16_16") (pintype "passive"))
    )
    (net (code "56") (name "Net-(IC8A-INH)") (class "Default")
      (node (ref "IC8") (pin "6") (pinfunction "INH_6") (pintype "input"))
      (node (ref "SEQUENCER") (pin "2") (pinfunction "P_2") (pintype "passive"))
    )
    (net (code "57") (name "Net-(IC8A-X0)") (class "Default")
      (node (ref "IC8") (pin "13") (pinfunction "X0_13") (pintype "bidirectional"))
      (node (ref "R34") (pin "P$2") (pinfunction "2_P$2") (pintype "passive"))
    )
    (net (code "58") (name "Net-(IC8A-X1)") (class "Default")
      (node (ref "IC8") (pin "14") (pinfunction "X1_14") (pintype "bidirectional"))
      (node (ref "R33") (pin "P$2") (pinfunction "2_P$2") (pintype "passive"))
    )
    (net (code "59") (name "Net-(IC8A-X2)") (class "Default")
      (node (ref "IC8") (pin "15") (pinfunction "X2_15") (pintype "bidirectional"))
      (node (ref "R32") (pin "P$2") (pinfunction "2_P$2") (pintype "passive"))
    )
    (net (code "60") (name "Net-(IC8A-X3)") (class "Default")
      (node (ref "IC8") (pin "12") (pinfunction "X3_12") (pintype "bidirectional"))
      (node (ref "R31") (pin "P$2") (pinfunction "2_P$2") (pintype "passive"))
    )
    (net (code "61") (name "Net-(IC8A-X4)") (class "Default")
      (node (ref "IC8") (pin "1") (pinfunction "X4_1") (pintype "bidirectional"))
      (node (ref "R30") (pin "P$2") (pinfunction "2_P$2") (pintype "passive"))
    )
    (net (code "62") (name "Net-(IC8A-X5)") (class "Default")
      (node (ref "IC8") (pin "5") (pinfunction "X5_5") (pintype "bidirectional"))
      (node (ref "R29") (pin "P$2") (pinfunction "2_P$2") (pintype "passive"))
    )
    (net (code "63") (name "Net-(IC8A-X6)") (class "Default")
      (node (ref "IC8") (pin "2") (pinfunction "X6_2") (pintype "bidirectional"))
      (node (ref "R28") (pin "P$2") (pinfunction "2_P$2") (pintype "passive"))
    )
    (net (code "64") (name "Net-(IC8A-X7)") (class "Default")
      (node (ref "IC8") (pin "4") (pinfunction "X7_4") (pintype "bidirectional"))
      (node (ref "R27") (pin "P$2") (pinfunction "2_P$2") (pintype "passive"))
    )
    (net (code "65") (name "Net-(Q1-B)") (class "Default")
      (node (ref "Q1") (pin "2") (pinfunction "B_2") (pintype "passive"))
      (node (ref "R27") (pin "P$1") (pinfunction "1_P$1") (pintype "passive"))
    )
    (net (code "66") (name "Net-(Q2-B)") (class "Default")
      (node (ref "Q2") (pin "2") (pinfunction "B_2") (pintype "passive"))
      (node (ref "R28") (pin "P$1") (pinfunction "1_P$1") (pintype "passive"))
    )
    (net (code "67") (name "Net-(Q3-B)") (class "Default")
      (node (ref "Q3") (pin "2") (pinfunction "B_2") (pintype "passive"))
      (node (ref "R29") (pin "P$1") (pinfunction "1_P$1") (pintype "passive"))
    )
    (net (code "68") (name "Net-(Q4-B)") (class "Default")
      (node (ref "Q4") (pin "2") (pinfunction "B_2") (pintype "passive"))
      (node (ref "R30") (pin "P$1") (pinfunction "1_P$1") (pintype "passive"))
    )
    (net (code "69") (name "Net-(Q5-B)") (class "Default")
      (node (ref "Q5") (pin "2") (pinfunction "B_2") (pintype "passive"))
      (node (ref "R31") (pin "P$1") (pinfunction "1_P$1") (pintype "passive"))
    )
    (net (code "70") (name "Net-(Q6-B)") (class "Default")
      (node (ref "Q6") (pin "2") (pinfunction "B_2") (pintype "passive"))
      (node (ref "R32") (pin "P$1") (pinfunction "1_P$1") (pintype "passive"))
    )
    (net (code "71") (name "Net-(Q7-B)") (class "Default")
      (node (ref "Q7") (pin "2") (pinfunction "B_2") (pintype "passive"))
      (node (ref "R33") (pin "P$1") (pinfunction "1_P$1") (pintype "passive"))
    )
    (net (code "72") (name "Net-(Q8-B)") (class "Default")
      (node (ref "Q8") (pin "2") (pinfunction "B_2") (pintype "passive"))
      (node (ref "R34") (pin "P$1") (pinfunction "1_P$1") (pintype "passive"))
    )
    (net (code "73") (name "Net-(R19-P$2)") (class "Default")
      (node (ref "R19") (pin "2") (pinfunction "P$2_2") (pintype "bidirectional"))
      (node (ref "R21") (pin "P$2") (pinfunction "2_P$2") (pintype "passive"))
    )
    (net (code "74") (name "Net-(R20-P$2)") (class "Default")
      (node (ref "R20") (pin "2") (pinfunction "P$2_2") (pintype "bidirectional"))
      (node (ref "R22") (pin "P$2") (pinfunction "2_P$2") (pintype "passive"))
    )
    (net (code "75") (name "Net-(R35-2)") (class "Default")
      (node (ref "R35") (pin "P$2") (pinfunction "2_P$2") (pintype "passive"))
      (node (ref "SEQUENCER") (pin "3") (pinfunction "S_3") (pintype "passive"))
    )
    (net (code "76") (name "VCC") (class "Default")
      (node (ref "IC1") (pin "8") (pinfunction "V+_8") (pintype "power_in"))
      (node (ref "IC2") (pin "8") (pinfunction "V+_8") (pintype "power_in"))
      (node (ref "IC3") (pin "8") (pinfunction "V+_8") (pintype "power_in"))
      (node (ref "IC4") (pin "8") (pinfunction "V+_8") (pintype "power_in"))
      (node (ref "IC5") (pin "8") (pinfunction "V+_8") (pintype "power_in"))
      (node (ref "IC6") (pin "14") (pinfunction "VDD_14") (pintype "power_in"))
      (node (ref "IC7") (pin "16") (pinfunction "VDD_16") (pintype "power_in"))
      (node (ref "IC8") (pin "16") (pinfunction "VCC_16") (pintype "power_in"))
      (node (ref "POWER") (pin "+") (pinfunction "+_+") (pintype "passive"))
      (node (ref "PWM") (pin "P$1") (pinfunction "E_P$1") (pintype "passive"))
      (node (ref "R1") (pin "P$2") (pinfunction "2_P$2") (pintype "passive"))
      (node (ref "R23") (pin "P$2") (pinfunction "2_P$2") (pintype "passive"))
      (node (ref "R6") (pin "P$2") (pinfunction "2_P$2") (pintype "passive"))
      (node (ref "SEQUENCER") (pin "1") (pinfunction "O_1") (pintype "passive"))
    )
    (net (code "77") (name "unconnected-(F1-A-PadP$3)") (class "Default")
      (node (ref "F1") (pin "P$3") (pinfunction "A_P$3") (pintype "passive"))
    )
    (net (code "78") (name "unconnected-(F2-A-PadP$3)") (class "Default")
      (node (ref "F2") (pin "P$3") (pinfunction "A_P$3") (pintype "passive"))
    )
    (net (code "79") (name "unconnected-(F3-A-PadP$3)") (class "Default")
      (node (ref "F3") (pin "P$3") (pinfunction "A_P$3") (pintype "passive"))
    )
    (net (code "80") (name "unconnected-(F4-A-PadP$3)") (class "Default")
      (node (ref "F4") (pin "P$3") (pinfunction "A_P$3") (pintype "passive"))
    )
    (net (code "81") (name "unconnected-(F5-A-PadP$3)") (class "Default")
      (node (ref "F5") (pin "P$3") (pinfunction "A_P$3") (pintype "passive"))
    )
    (net (code "82") (name "unconnected-(F6-A-PadP$3)") (class "Default")
      (node (ref "F6") (pin "P$3") (pinfunction "A_P$3") (pintype "passive"))
    )
    (net (code "83") (name "unconnected-(F7-A-PadP$3)") (class "Default")
      (node (ref "F7") (pin "P$3") (pinfunction "A_P$3") (pintype "passive"))
    )
    (net (code "84") (name "unconnected-(F8-A-PadP$3)") (class "Default")
      (node (ref "F8") (pin "P$3") (pinfunction "A_P$3") (pintype "passive"))
    )
    (net (code "85") (name "unconnected-(IC5B-+IN-Pad5)") (class "Default")
      (node (ref "IC5") (pin "5") (pinfunction "+IN_5") (pintype "input"))
    )
    (net (code "86") (name "unconnected-(IC7A-Q5-Pad3)") (class "Default")
      (node (ref "IC7") (pin "3") (pinfunction "Q5_3") (pintype "output"))
    )
    (net (code "87") (name "unconnected-(IC7A-Q6-Pad2)") (class "Default")
      (node (ref "IC7") (pin "2") (pinfunction "Q6_2") (pintype "output"))
    )
    (net (code "88") (name "unconnected-(IC7A-Q8-Pad13)") (class "Default")
      (node (ref "IC7") (pin "13") (pinfunction "Q8_13") (pintype "output"))
    )
    (net (code "89") (name "unconnected-(IC7A-Q10-Pad14)") (class "Default")
      (node (ref "IC7") (pin "14") (pinfunction "Q10_14") (pintype "output"))
    )
    (net (code "90") (name "unconnected-(IC7A-Q11-Pad15)") (class "Default")
      (node (ref "IC7") (pin "15") (pinfunction "Q11_15") (pintype "output"))
    )
    (net (code "91") (name "unconnected-(IC7A-Q12-Pad1)") (class "Default")
      (node (ref "IC7") (pin "1") (pinfunction "Q12_1") (pintype "output"))
    )
    (net (code "92") (name "unconnected-(VR1-E-PadP$1)") (class "Default")
      (node (ref "VR1") (pin "P$1") (pinfunction "E_P$1") (pintype "passive"))
    )
  )
)
